# P03_UART_Debug.net
KiCad netlist of a schematic drawn in Altium Designer
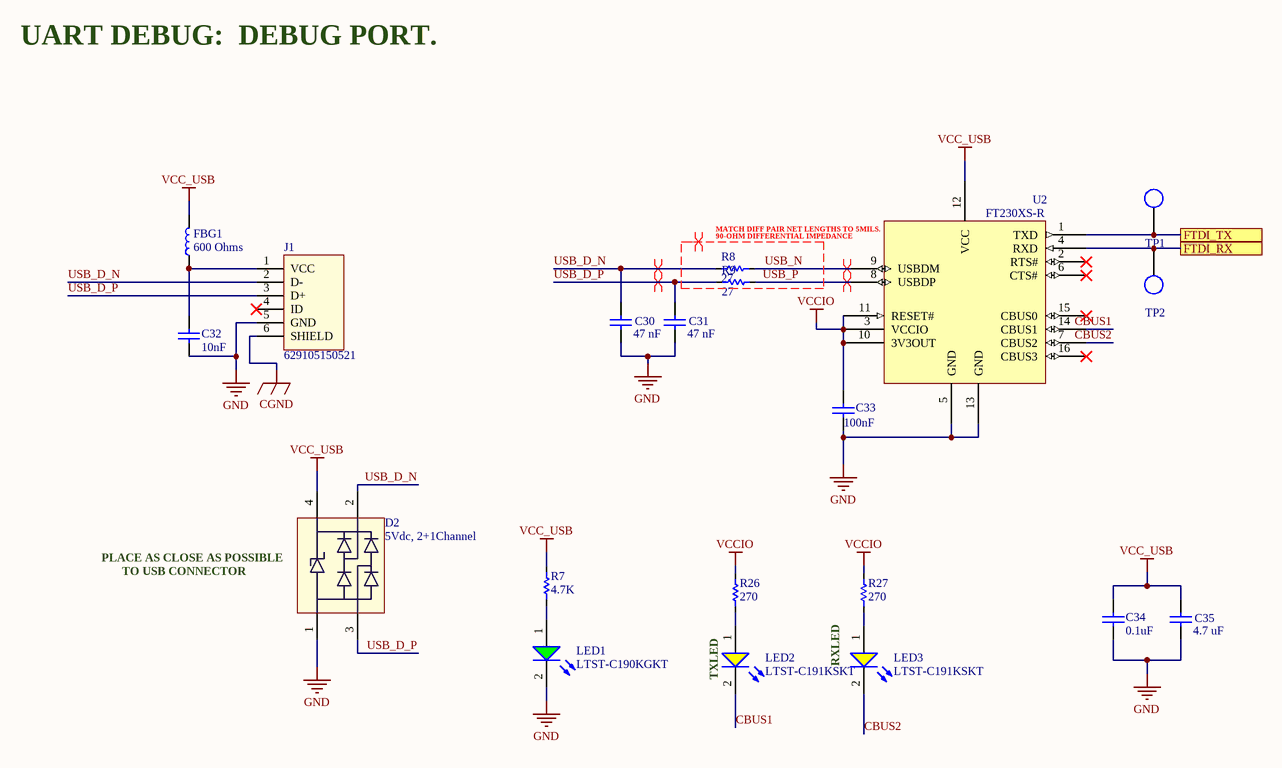
[diagram p0: P03_UART_Debug.SchDoc]

(export (version "E")
  (design (tool "Eeschema 10.0.6"))
  (components
    (comp (ref "C30")
      (value "47 nF")
      (footprint "CAP_0603")
      (description "CAP CER 0.047UF 16V X7R 0603")
      (fields (field (name "MANUFACTURER PART NO.") "C0603C473K4RACTU") (field (name "MANUFACTURER") "KEMET"))
      (libsource (lib "Felix_Sch_lib") (part "C0603C473K4RACTU"))
    )
    (comp (ref "C31")
      (value "47 nF")
      (footprint "CAP_0603")
      (description "CAP CER 0.047UF 16V X7R 0603")
      (fields (field (name "MANUFACTURER PART NO.") "C0603C473K4RACTU") (field (name "MANUFACTURER") "KEMET"))
      (libsource (lib "Felix_Sch_lib") (part "C0603C473K4RACTU"))
    )
    (comp (ref "C32")
      (value "10nF")
      (footprint "CAP_0603")
      (description "CAP CER 10000PF 16V NPO 0805")
      (fields
        (field (name "MANUFACTURER") "Yageo")
        (field (name "MANUFACTURER PART NO.") "CC0805JKNPO7BN103")
      )
      (libsource (lib "Felix_Sch_lib") (part "C0603C104M4RACTU"))
    )
    (comp (ref "C33")
      (value "100nF")
      (footprint "CAP_0603")
      (description "CAP CER 100PF 16V NP0 0603")
      (fields
        (field (name "MANUFACTURER") "KEMET")
        (field (name "MANUFACTURER PART NO.") "C0603C101J4GAC7867")
      )
      (libsource (lib "Felix_Sch_lib") (part "C0603C104M4RACTU"))
    )
    (comp (ref "C34")
      (value "0.1uF")
      (footprint "CAP_0603")
      (description "CAP CER 0.1UF 16V X5R 0603")
      (fields
        (field (name "MANUFACTURER") "KEMET")
        (field (name "MANUFACTURER PART NO.") "C0603C104K4PAC7867")
      )
      (libsource (lib "Felix_Sch_lib") (part "C0603C104K4PAC7867"))
    )
    (comp (ref "C35")
      (value "4.7 uF")
      (footprint "CAP_0603")
      (description "CAP CER 4.7UF 16V X5R 0603")
      (fields
        (field (name "MANUFACTURER PART NO.") "GRM188R61C475KAAJD")
        (field (name "MANUFACTURER") "Murata Electronics")
      )
      (libsource (lib "Felix_Sch_lib") (part "C0603C473K4RACTU_1"))
    )
    (comp (ref "D2")
      (value "5Vdc, 2+1Channel")
      (footprint "SOT143-4L")
      (description "TVS DIODE 5V 9V SOT143-4 ESD")
      (fields
        (field (name "MANUFACTURER") "Wurth Elektronik")
        (field (name "MANUFACTURER PART NO.") "8240026")
      )
      (libsource (lib "OSD335-X_Devboard") (part "8240026"))
    )
    (comp (ref "FBG1")
      (value "600 Ohms")
      (footprint "CAP_0603")
      (description "600 Ohms @ 100MHz Ferrite Bead 0603 2A 100mOhm")
      (fields
        (field (name "MANUFACTURER") "Chilisin Electronics")
        (field (name "MANUFACTURER PART NO.") "BBHV00160808601Y00")
      )
      (libsource (lib "Felix_Sch_lib") (part "Ferrite Bead Generic"))
    )
    (comp (ref "J1")
      (value "629105150521")
      (footprint "629105150521")
      (description "CONN RCPT USB2.0 MICRO B SMD R/A")
      (fields (field (name "MANUFACTURER") "Wurth Elektronik"))
      (libsource (lib "OSD335-X_Devboard") (part "629105150521"))
    )
    (comp (ref "LED1")
      (value "LTST-C190KGKT")
      (footprint "OSD335-X_Devboard:LED_0603")
      (description "LED GREEN CLEAR CHIP SMD 0603")
      (fields (field (name "MANUFACTURER") "Lite-On Inc."))
      (libsource (lib "OSD335-X_Devboard") (part "LTST-C190KGKT"))
    )
    (comp (ref "LED2")
      (value "LTST-C191KSKT")
      (footprint "LED_0603")
      (description "LED YELLOW CLEAR SMD 0603")
      (fields (field (name "MANUFACTURER") "Lite-On Inc."))
      (libsource (lib "Felix_Sch_lib") (part "LTST-C191KSKT"))
    )
    (comp (ref "LED3")
      (value "LTST-C191KSKT")
      (footprint "LED_0603")
      (description "LED YELLOW CLEAR SMD 0603")
      (fields (field (name "MANUFACTURER") "Lite-On Inc."))
      (libsource (lib "Felix_Sch_lib") (part "LTST-C191KSKT"))
    )
    (comp (ref "R7")
      (value "4.7K")
      (footprint "RES_0603")
      (description "RES SMD 4.7K OHM 5% 1/10W 0603")
      (fields (field (name "TOLERANCE") "5%") (field (name "MANUFACTURER") "Yageo"))
      (libsource (lib "OSD335-X_Devboard") (part "RC0603JR-074K7L"))
    )
    (comp (ref "R8")
      (value "27")
      (footprint "RES_0603")
      (description "RES SMD 27 OHM 5% 1/10W 0603")
      (fields (field (name "TOLERANCE") "5%") (field (name "MANUFACTURER") "Yageo"))
      (libsource (lib "OSD335-X_Devboard") (part "RC0603JR-0727RL"))
    )
    (comp (ref "R9")
      (value "27")
      (footprint "RES_0603")
      (description "RES SMD 27 OHM 5% 1/10W 0603")
      (fields (field (name "TOLERANCE") "5%") (field (name "MANUFACTURER") "Yageo"))
      (libsource (lib "OSD335-X_Devboard") (part "RC0603JR-0727RL"))
    )
    (comp (ref "R26")
      (value "270")
      (footprint "RES_0603")
      (description "RES SMD 270 OHM 5% 1/10W 0603")
      (fields (field (name "TOLERANCE") "5%") (field (name "MANUFACTURER") "Yageo"))
      (libsource (lib "Felix_Sch_lib") (part "RC0603JR-07270RL"))
    )
    (comp (ref "R27")
      (value "270")
      (footprint "RES_0603")
      (description "RES SMD 270 OHM 5% 1/10W 0603")
      (fields (field (name "TOLERANCE") "5%") (field (name "MANUFACTURER") "Yageo"))
      (libsource (lib "Felix_Sch_lib") (part "RC0603JR-07270RL"))
    )
    (comp (ref "TP1")
      (value "TP_SMD")
      (footprint "TP_SMD")
      (libsource (lib "OSD335-X_Devboard") (part "TP_SMD"))
    )
    (comp (ref "TP2")
      (value "TP_SMD")
      (footprint "TP_SMD")
      (libsource (lib "OSD335-X_Devboard") (part "TP_SMD"))
    )
    (comp (ref "U2")
      (value "FT230XS-R")
      (footprint "SOP64P600X175-16N")
      (description "IC USB SERIAL BASIC UART 16SSOP")
      (fields (field (name "MANUFACTURER") "FTDI, Future Technology Devices International Ltd"))
      (libsource (lib "OSD335-X_Devboard") (part "FT230XS-R"))
    )
  )
  (nets
    (net (code "1") (name "/CBUS1") (class "Default")
      (node (ref "LED2") (pin "2") (pinfunction "C_2") (pintype "passive"))
      (node (ref "U2") (pin "14") (pinfunction "CBUS1_14") (pintype "bidirectional"))
    )
    (net (code "2") (name "/CBUS2") (class "Default")
      (node (ref "LED3") (pin "2") (pinfunction "C_2") (pintype "passive"))
      (node (ref "U2") (pin "7") (pinfunction "CBUS2_7") (pintype "bidirectional"))
    )
    (net (code "3") (name "/FTDI_RX") (class "Default")
      (node (ref "TP2") (pin "1") (pinfunction "1_1") (pintype "passive"))
      (node (ref "U2") (pin "4") (pinfunction "RXD_4") (pintype "input"))
    )
    (net (code "4") (name "/FTDI_TX") (class "Default")
      (node (ref "TP1") (pin "1") (pinfunction "1_1") (pintype "passive"))
      (node (ref "U2") (pin "1") (pinfunction "TXD_1") (pintype "output"))
    )
    (net (code "5") (name "/USB_D_N") (class "Default")
      (node (ref "C30") (pin "1") (pinfunction "N_1") (pintype "passive"))
      (node (ref "D2") (pin "2") (pinfunction "IO1_2") (pintype "passive"))
      (node (ref "J1") (pin "2") (pinfunction "D-_2") (pintype "passive"))
      (node (ref "R8") (pin "1") (pinfunction "1_1") (pintype "passive"))
    )
    (net (code "6") (name "/USB_D_P") (class "Default")
      (node (ref "C31") (pin "1") (pinfunction "N_1") (pintype "passive"))
      (node (ref "D2") (pin "3") (pinfunction "IO2_3") (pintype "passive"))
      (node (ref "J1") (pin "3") (pinfunction "D+_3") (pintype "passive"))
      (node (ref "R9") (pin "1") (pinfunction "1_1") (pintype "passive"))
    )
    (net (code "7") (name "/USB_N") (class "Default")
      (node (ref "R8") (pin "2") (pinfunction "2_2") (pintype "passive"))
      (node (ref "U2") (pin "9") (pinfunction "USBDM_9") (pintype "bidirectional"))
    )
    (net (code "8") (name "/USB_P") (class "Default")
      (node (ref "R9") (pin "2") (pinfunction "2_2") (pintype "passive"))
      (node (ref "U2") (pin "8") (pinfunction "USBDP_8") (pintype "bidirectional"))
    )
    (net (code "9") (name "CGND") (class "Default")
      (node (ref "J1") (pin "6") (pinfunction "SHIELD_6") (pintype "passive"))
    )
    (net (code "10") (name "GND") (class "Default")
      (node (ref "C30") (pin "2") (pinfunction "P_2") (pintype "passive"))
      (node (ref "C31") (pin "2") (pinfunction "P_2") (pintype "passive"))
      (node (ref "C32") (pin "1") (pinfunction "1_1") (pintype "passive"))
      (node (ref "C33") (pin "1") (pinfunction "1_1") (pintype "passive"))
      (node (ref "C34") (pin "1") (pinfunction "1_1") (pintype "passive"))
      (node (ref "C35") (pin "1") (pinfunction "N_1") (pintype "passive"))
      (node (ref "D2") (pin "1") (pinfunction "GND_1") (pintype "passive"))
      (node (ref "J1") (pin "5") (pinfunction "GND_5") (pintype "passive"))
      (node (ref "LED1") (pin "2") (pinfunction "C_2") (pintype "passive"))
      (node (ref "U2") (pin "13") (pinfunction "GND_13") (pintype "power_in"))
      (node (ref "U2") (pin "5") (pinfunction "GND_5") (pintype "power_in"))
    )
    (net (code "11") (name "Net-(J1-VCC)") (class "Default")
      (node (ref "C32") (pin "2") (pinfunction "2_2") (pintype "passive"))
      (node (ref "FBG1") (pin "1") (pinfunction "1_1") (pintype "passive"))
      (node (ref "J1") (pin "1") (pinfunction "VCC_1") (pintype "passive"))
    )
    (net (code "12") (name "Net-(LED1-A)") (class "Default")
      (node (ref "LED1") (pin "1") (pinfunction "A_1") (pintype "passive"))
      (node (ref "R7") (pin "1") (pinfunction "1_1") (pintype "passive"))
    )
    (net (code "13") (name "Net-(LED2-A)") (class "Default")
      (node (ref "LED2") (pin "1") (pinfunction "A_1") (pintype "passive"))
      (node (ref "R26") (pin "1") (pinfunction "1_1") (pintype "passive"))
    )
    (net (code "14") (name "Net-(LED3-A)") (class "Default")
      (node (ref "LED3") (pin "1") (pinfunction "A_1") (pintype "passive"))
      (node (ref "R27") (pin "1") (pinfunction "1_1") (pintype "passive"))
    )
    (net (code "15") (name "VCCIO") (class "Default")
      (node (ref "C33") (pin "2") (pinfunction "2_2") (pintype "passive"))
      (node (ref "R26") (pin "2") (pinfunction "2_2") (pintype "passive"))
      (node (ref "R27") (pin "2") (pinfunction "2_2") (pintype "passive"))
      (node (ref "U2") (pin "10") (pinfunction "3V3OUT_10") (pintype "power_in"))
      (node (ref "U2") (pin "11") (pinfunction "RESET#_11") (pintype "input"))
      (node (ref "U2") (pin "3") (pinfunction "VCCIO_3") (pintype "power_in"))
    )
    (net (code "16") (name "VCC_USB") (class "Default")
      (node (ref "C34") (pin "2") (pinfunction "2_2") (pintype "passive"))
      (node (ref "C35") (pin "2") (pinfunction "P_2") (pintype "passive"))
      (node (ref "D2") (pin "4") (pinfunction "VDD_4") (pintype "passive"))
      (node (ref "FBG1") (pin "2") (pinfunction "2_2") (pintype "passive"))
      (node (ref "R7") (pin "2") (pinfunction "2_2") (pintype "passive"))
      (node (ref "U2") (pin "12") (pinfunction "VCC_12") (pintype "power_in"))
    )
    (net (code "17") (name "unconnected-(J1-ID-Pad4)") (class "Default")
      (node (ref "J1") (pin "4") (pinfunction "ID_4") (pintype "passive+no_connect"))
    )
    (net (code "18") (name "unconnected-(U2-CBUS0-Pad15)") (class "Default")
      (node (ref "U2") (pin "15") (pinfunction "CBUS0_15") (pintype "bidirectional+no_connect"))
    )
    (net (code "19") (name "unconnected-(U2-CBUS3-Pad16)") (class "Default")
      (node (ref "U2") (pin "16") (pinfunction "CBUS3_16") (pintype "bidirectional+no_connect"))
    )
    (net (code "20") (name "unconnected-(U2-CTS#-Pad6)") (class "Default")
      (node (ref "U2") (pin "6") (pinfunction "CTS#_6") (pintype "bidirectional+no_connect"))
    )
    (net (code "21") (name "unconnected-(U2-RTS#-Pad2)") (class "Default")
      (node (ref "U2") (pin "2") (pinfunction "RTS#_2") (pintype "bidirectional+no_connect"))
    )
  )
)
